# design.net
KiCad netlist of a schematic drawn in Altium Designer
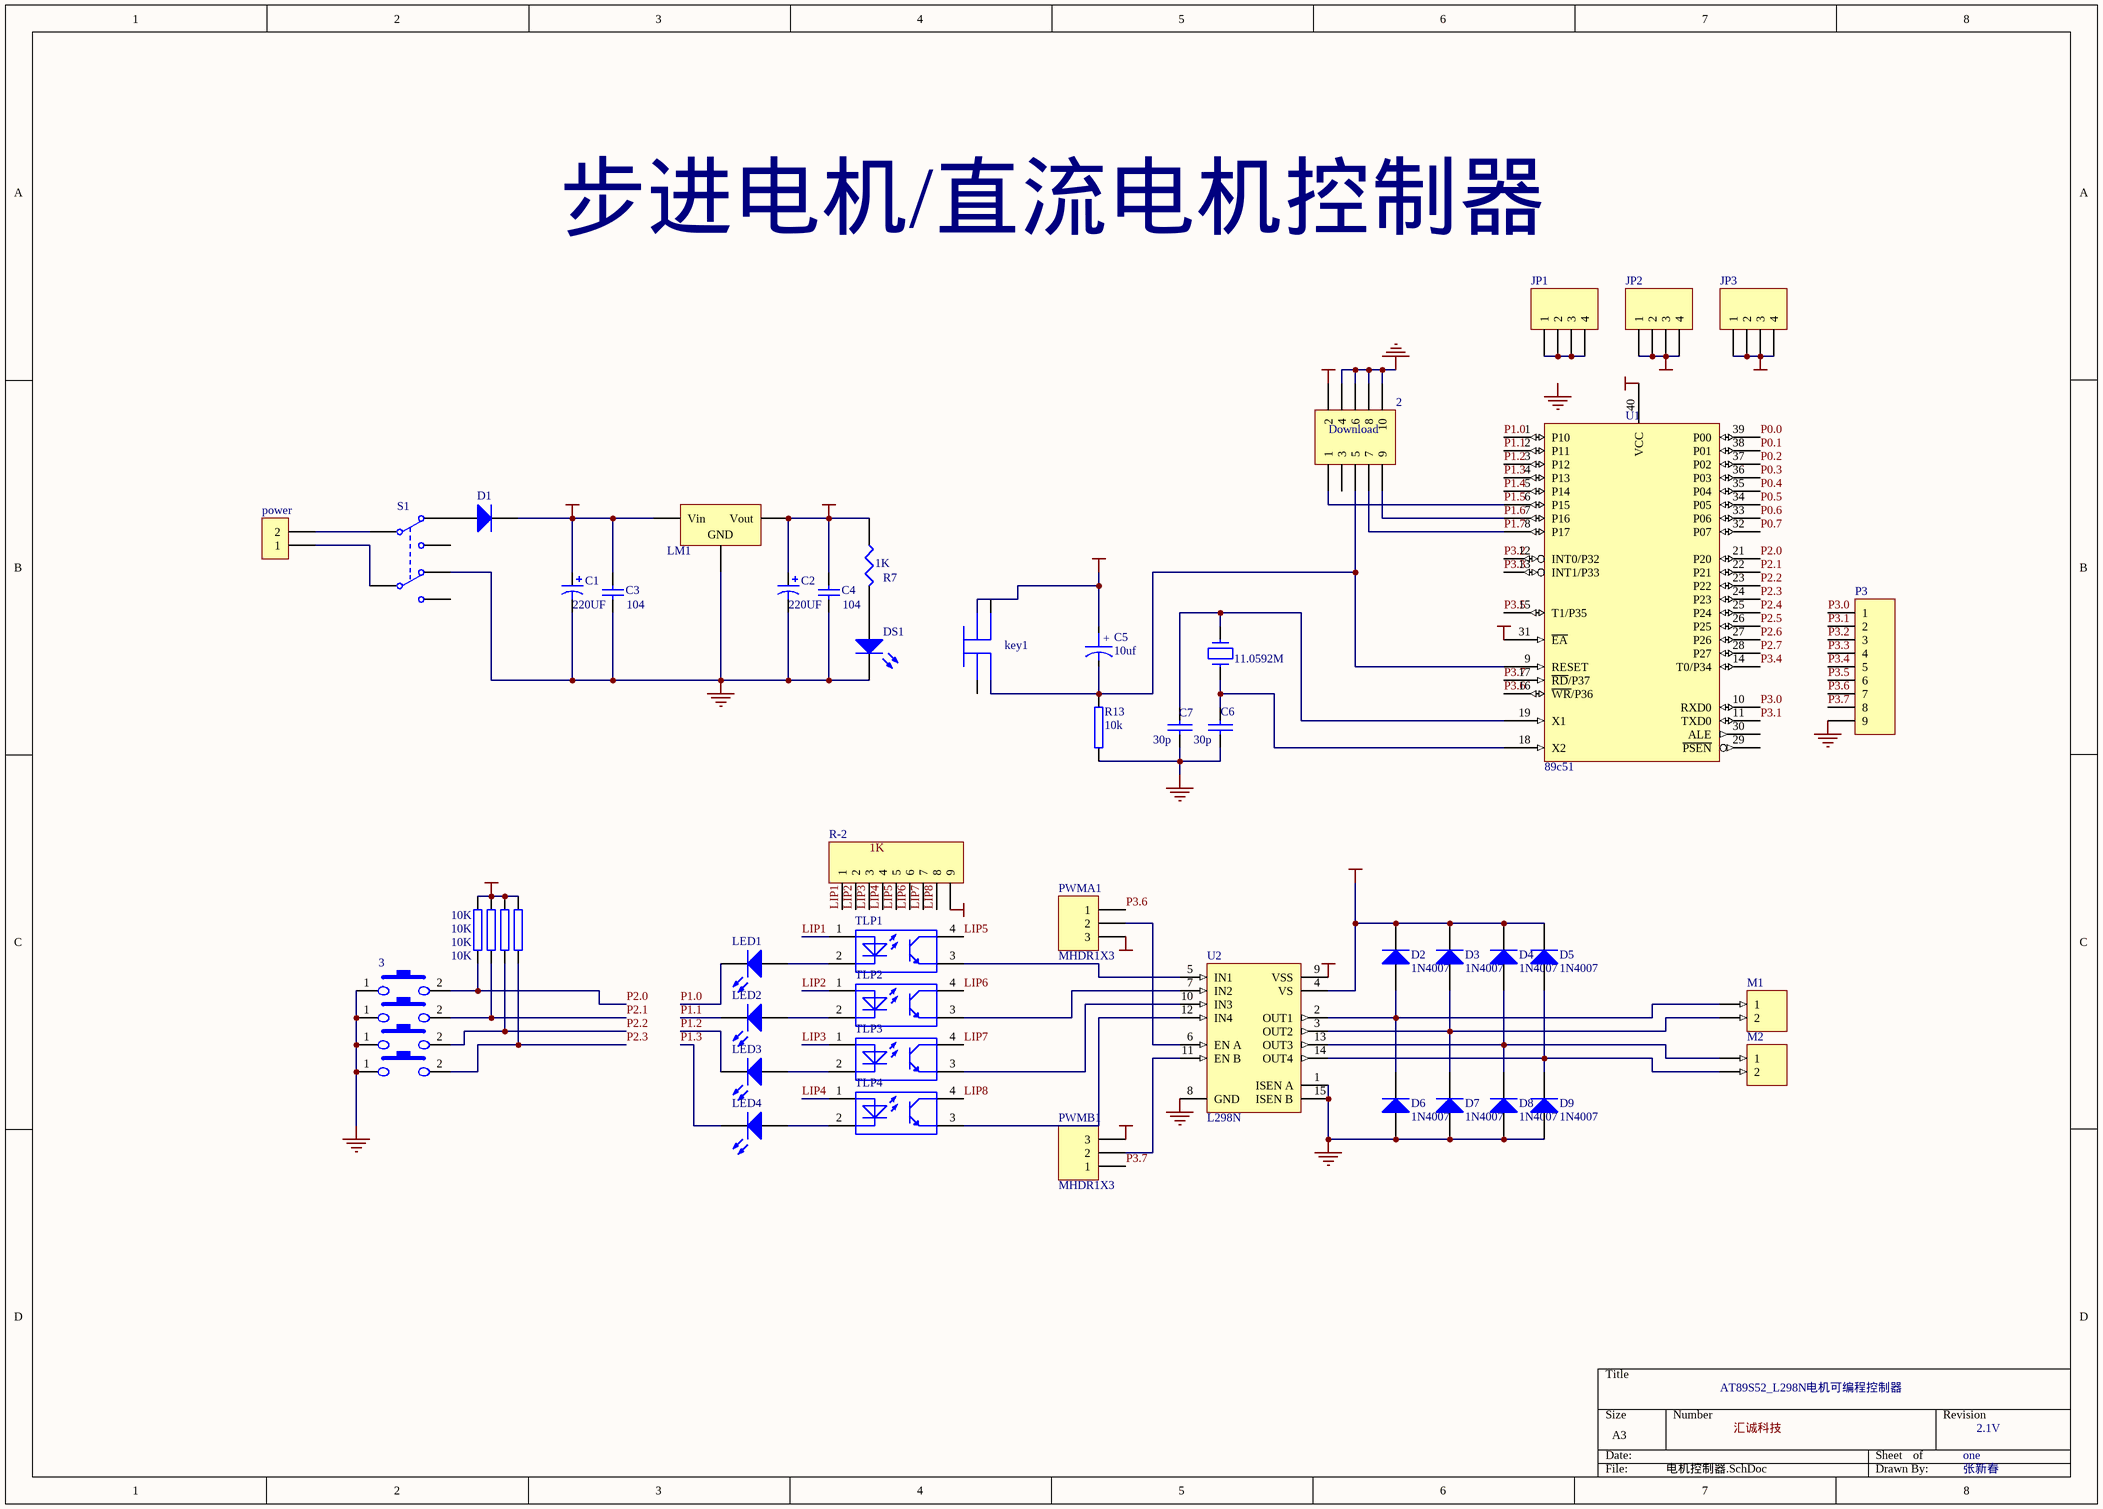
[diagram p0: 电机控制器.SchDoc]

(export (version "E")
  (design (tool "Eeschema 10.0.6"))
  (components
    (comp (ref "1")
      (value "power")
      (footprint "jiechajian:DZ-2")
      (libsource (lib "OldCow1 (1)") (part "power"))
    )
    (comp (ref "2")
      (value "Download")
      (footprint "HDR2X5")
      (description "Header, 5-Pin, Dual row")
      (fields (field (name "PUBLISHER") "Altium Limited"))
      (libsource (lib "Miscellaneous Connectors") (part "Header 5X2"))
    )
    (comp (ref "3") (value "key1") (footprint "AN66") (libsource (lib "OldCow1 (1)") (part "key")))
    (comp (ref "4") (value "key2") (footprint "AN66") (libsource (lib "OldCow1 (1)") (part "key")))
    (comp (ref "5") (value "key3") (footprint "AN66") (libsource (lib "OldCow1 (1)") (part "key")))
    (comp (ref "6") (value "key4") (footprint "AN66") (libsource (lib "OldCow1 (1)") (part "key")))
    (comp (ref "C1")
      (value "220UF")
      (footprint "CD6")
      (description "Polarized Capacitor (Radial)")
      (fields (field (name "PUBLISHER") "Altium Limited"))
      (libsource (lib "Miscellaneous Devices") (part "Cap Pol1"))
    )
    (comp (ref "C2")
      (value "220UF")
      (footprint "CD4")
      (description "Polarized Capacitor (Radial)")
      (fields (field (name "PUBLISHER") "Altium Limited"))
      (libsource (lib "Miscellaneous Devices") (part "Cap Pol1"))
    )
    (comp (ref "C3")
      (value "104")
      (footprint "HDR1X2")
      (description "Capacitor")
      (fields (field (name "PUBLISHER") "Altium Limited"))
      (libsource (lib "Miscellaneous Devices") (part "Cap"))
    )
    (comp (ref "C4")
      (value "104")
      (footprint "HDR1X2")
      (description "Capacitor")
      (fields (field (name "PUBLISHER") "Altium Limited"))
      (libsource (lib "Miscellaneous Devices") (part "Cap"))
    )
    (comp (ref "C5")
      (value "10uf")
      (footprint "CD5")
      (description "Capacitor")
      (libsource (lib "*") (part "CAPACITOR POL"))
    )
    (comp (ref "C6")
      (value "30p")
      (footprint "C1608-0603")
      (description "Capacitor")
      (libsource (lib "*") (part "CAP"))
    )
    (comp (ref "C7")
      (value "30p")
      (footprint "C1608-0603")
      (description "Capacitor")
      (libsource (lib "*") (part "CAP"))
    )
    (comp (ref "D1")
      (value "~")
      (footprint "DIO10.46-5.3x2.8")
      (description "1 Amp General Purpose Rectifier")
      (fields (field (name "PUBLISHER") "Altium Limited"))
      (libsource (lib "Miscellaneous Devices") (part "Diode 1N4007"))
    )
    (comp (ref "D2")
      (value "1N4007")
      (footprint "DIO7.8-4.6x2")
      (description "1 Amp General Purpose Rectifier")
      (fields (field (name "PUBLISHER") "Altium Limited"))
      (libsource (lib "Miscellaneous Devices") (part "Diode 1N4007"))
    )
    (comp (ref "D3")
      (value "1N4007")
      (footprint "DIO7.8-4.6x2")
      (description "1 Amp General Purpose Rectifier")
      (fields (field (name "PUBLISHER") "Altium Limited"))
      (libsource (lib "Miscellaneous Devices") (part "Diode 1N4007"))
    )
    (comp (ref "D4")
      (value "1N4007")
      (footprint "DIO7.8-4.6x2")
      (description "1 Amp General Purpose Rectifier")
      (fields (field (name "PUBLISHER") "Altium Limited"))
      (libsource (lib "Miscellaneous Devices") (part "Diode 1N4007"))
    )
    (comp (ref "D5")
      (value "1N4007")
      (footprint "DIO7.8-4.6x2")
      (description "1 Amp General Purpose Rectifier")
      (fields (field (name "PUBLISHER") "Altium Limited"))
      (libsource (lib "Miscellaneous Devices") (part "Diode 1N4007"))
    )
    (comp (ref "D6")
      (value "1N4007")
      (footprint "DIO7.8-4.6x2")
      (description "1 Amp General Purpose Rectifier")
      (fields (field (name "PUBLISHER") "Altium Limited"))
      (libsource (lib "Miscellaneous Devices") (part "Diode 1N4007"))
    )
    (comp (ref "D7")
      (value "1N4007")
      (footprint "DIO7.8-4.6x2")
      (description "1 Amp General Purpose Rectifier")
      (fields (field (name "PUBLISHER") "Altium Limited"))
      (libsource (lib "Miscellaneous Devices") (part "Diode 1N4007"))
    )
    (comp (ref "D8")
      (value "1N4007")
      (footprint "DIO7.8-4.6x2")
      (description "1 Amp General Purpose Rectifier")
      (fields (field (name "PUBLISHER") "Altium Limited"))
      (libsource (lib "Miscellaneous Devices") (part "Diode 1N4007"))
    )
    (comp (ref "D9")
      (value "1N4007")
      (footprint "DIO7.8-4.6x2")
      (description "1 Amp General Purpose Rectifier")
      (fields (field (name "PUBLISHER") "Altium Limited"))
      (libsource (lib "Miscellaneous Devices") (part "Diode 1N4007"))
    )
    (comp (ref "DS1")
      (value "~")
      (footprint "HDR1X2")
      (description "Typical INFRARED GaAs LED")
      (fields (field (name "PUBLISHER") "Altium Limited"))
      (libsource (lib "Miscellaneous Devices") (part "LED0"))
    )
    (comp (ref "JP1")
      (value "~")
      (footprint "HDR1X4")
      (description "Header, 4-Pin")
      (fields (field (name "PUBLISHER") "Altium Limited"))
      (libsource (lib "Miscellaneous Connectors") (part "Header 4"))
    )
    (comp (ref "JP2")
      (value "~")
      (footprint "HDR1X4")
      (description "Header, 4-Pin")
      (fields (field (name "PUBLISHER") "Altium Limited"))
      (libsource (lib "Miscellaneous Connectors") (part "Header 4"))
    )
    (comp (ref "JP3")
      (value "~")
      (footprint "HDR1X4")
      (description "Header, 4-Pin")
      (fields (field (name "PUBLISHER") "Altium Limited"))
      (libsource (lib "Miscellaneous Connectors") (part "Header 4"))
    )
    (comp (ref "key1") (value "KEY") (footprint "AN66") (libsource (lib "OldCow1 (1)") (part "KEY")))
    (comp (ref "LED1")
      (value "~")
      (footprint "HDR1X2")
      (description "Typical BLUE SiC LED")
      (fields (field (name "PUBLISHER") "Altium Limited"))
      (libsource (lib "Miscellaneous Devices") (part "LED3"))
    )
    (comp (ref "LED2")
      (value "~")
      (footprint "HDR1X2")
      (description "Typical BLUE SiC LED")
      (fields (field (name "PUBLISHER") "Altium Limited"))
      (libsource (lib "Miscellaneous Devices") (part "LED3"))
    )
    (comp (ref "LED3")
      (value "~")
      (footprint "HDR1X2")
      (description "Typical BLUE SiC LED")
      (fields (field (name "PUBLISHER") "Altium Limited"))
      (libsource (lib "Miscellaneous Devices") (part "LED3"))
    )
    (comp (ref "LED4")
      (value "~")
      (footprint "HDR1X2")
      (description "Typical BLUE SiC LED")
      (fields (field (name "PUBLISHER") "Altium Limited"))
      (libsource (lib "Miscellaneous Devices") (part "LED3"))
    )
    (comp (ref "LM1")
      (value "~")
      (footprint "wyk")
      (description "Voltage Regulator")
      (fields (field (name "PUBLISHER") "Altium Limited"))
      (libsource (lib "Miscellaneous Devices") (part "Volt Reg"))
    )
    (comp (ref "M1")
      (value "~")
      (footprint "DZ-2")
      (description "Header, 2-Pin")
      (fields (field (name "PUBLISHER") "Altium Limited"))
      (libsource (lib "Miscellaneous Connectors") (part "MHDR1X2"))
    )
    (comp (ref "M2")
      (value "~")
      (footprint "jiechajian:DZ-2")
      (description "Header, 2-Pin")
      (fields (field (name "PUBLISHER") "Altium Limited"))
      (libsource (lib "Miscellaneous Connectors") (part "MHDR1X2"))
    )
    (comp (ref "P3")
      (value "~")
      (footprint "HDR1X9")
      (description "Header, 9-Pin")
      (fields (field (name "PUBLISHER") "Altium Limited"))
      (libsource (lib "Miscellaneous Connectors") (part "Header 9"))
    )
    (comp (ref "PWMA1")
      (value "MHDR1X3")
      (footprint "MHDR1X3")
      (description "Header, 3-Pin")
      (fields (field (name "PUBLISHER") "Altium Limited"))
      (libsource (lib "Miscellaneous Connectors") (part "MHDR1X3"))
    )
    (comp (ref "PWMB1")
      (value "MHDR1X3")
      (footprint "MHDR1X3")
      (description "Header, 3-Pin")
      (fields (field (name "PUBLISHER") "Altium Limited"))
      (libsource (lib "") (part "MHDR1X3_1"))
    )
    (comp (ref "R-2")
      (value "~")
      (footprint "HDR1X9")
      (description "Header, 9-Pin")
      (fields (field (name "PUBLISHER") "Altium Limited"))
      (libsource (lib "") (part "Header 9_1"))
    )
    (comp (ref "R7") (value "1K") (footprint "HDR1X2") (libsource (lib "*") (part "RES1")))
    (comp (ref "R13") (value "10k") (footprint "INDC2012-0805") (libsource (lib "*") (part "RES2")))
    (comp (ref "R15") (value "10K") (footprint "INDC2012-0805") (libsource (lib "*") (part "RES2")))
    (comp (ref "R16") (value "10K") (footprint "INDC2012-0805") (libsource (lib "*") (part "RES2")))
    (comp (ref "R17") (value "10K") (footprint "INDC2012-0805") (libsource (lib "*") (part "RES2")))
    (comp (ref "R18") (value "10K") (footprint "INDC2012-0805") (libsource (lib "*") (part "RES2")))
    (comp (ref "S1")
      (value "~")
      (footprint "DPDT-6")
      (description "Switch")
      (fields (field (name "PUBLISHER") "Altium Limited"))
      (libsource (lib "Miscellaneous Devices") (part "SW DPDT"))
    )
    (comp (ref "TLP1") (value "~") (footprint "DIP4") (libsource (lib "MyInt_Lib") (part "TLP521-1")))
    (comp (ref "TLP2") (value "~") (footprint "DIP4") (libsource (lib "MyInt_Lib") (part "TLP521-1")))
    (comp (ref "TLP3") (value "~") (footprint "DIP4") (libsource (lib "MyInt_Lib") (part "TLP521-1")))
    (comp (ref "TLP4") (value "~") (footprint "DIP4") (libsource (lib "MyInt_Lib") (part "TLP521-1")))
    (comp (ref "U1") (value "89c51") (footprint "DIP40") (libsource (lib "OldCow1 (2)") (part "8051")))
    (comp (ref "U2")
      (value "L298N")
      (footprint "DFM-T15/X1.6V")
      (description "Dual Full Bridge Driver")
      (fields (field (name "PUBLISHER") "Altium Limited"))
      (libsource (lib "ST Interface DC Motor Controller") (part "L298N"))
    )
    (comp (ref "Y1")
      (value "11.0592M")
      (footprint "SPST-2")
      (description "Crystal")
      (libsource (lib "*") (part "CRYSTAL"))
    )
  )
  (nets
    (net (code "1") (name "+5V") (class "Default")
      (node (ref "2") (pin "2") (pinfunction "2_2") (pintype "passive"))
      (node (ref "C2") (pin "1") (pinfunction "1_1") (pintype "passive"))
      (node (ref "C4") (pin "2") (pinfunction "2_2") (pintype "passive"))
      (node (ref "C5") (pin "1") (pinfunction "1_1") (pintype "passive"))
      (node (ref "JP2") (pin "1") (pinfunction "1_1") (pintype "passive"))
      (node (ref "JP2") (pin "2") (pinfunction "2_2") (pintype "passive"))
      (node (ref "JP2") (pin "3") (pinfunction "3_3") (pintype "passive"))
      (node (ref "JP2") (pin "4") (pinfunction "4_4") (pintype "passive"))
      (node (ref "LM1") (pin "3") (pinfunction "Vout_3") (pintype "passive"))
      (node (ref "PWMA1") (pin "3") (pinfunction "3_3") (pintype "passive"))
      (node (ref "PWMB1") (pin "3") (pinfunction "3_3") (pintype "passive"))
      (node (ref "R-2") (pin "9") (pinfunction "9_9") (pintype "passive"))
      (node (ref "R15") (pin "2") (pinfunction "2_2") (pintype "passive"))
      (node (ref "R16") (pin "2") (pinfunction "2_2") (pintype "passive"))
      (node (ref "R17") (pin "2") (pinfunction "2_2") (pintype "passive"))
      (node (ref "R18") (pin "2") (pinfunction "2_2") (pintype "passive"))
      (node (ref "R7") (pin "1") (pinfunction "1_1") (pintype "passive"))
      (node (ref "U1") (pin "31") (pinfunction "~{EA}_31") (pintype "input"))
      (node (ref "U1") (pin "40") (pinfunction "VCC_40") (pintype "power_in"))
      (node (ref "U2") (pin "9") (pinfunction "VSS_9") (pintype "power_in"))
      (node (ref "key1") (pin "1") (pinfunction "1_1") (pintype "passive"))
    )
    (net (code "2") (name "+12V") (class "Default")
      (node (ref "C1") (pin "1") (pinfunction "1_1") (pintype "passive"))
      (node (ref "C3") (pin "2") (pinfunction "2_2") (pintype "passive"))
      (node (ref "D1") (pin "2") (pinfunction "K_2") (pintype "passive"))
      (node (ref "D2") (pin "2") (pinfunction "K_2") (pintype "passive"))
      (node (ref "D3") (pin "2") (pinfunction "K_2") (pintype "passive"))
      (node (ref "D4") (pin "2") (pinfunction "K_2") (pintype "passive"))
      (node (ref "D5") (pin "2") (pinfunction "K_2") (pintype "passive"))
      (node (ref "JP3") (pin "1") (pinfunction "1_1") (pintype "passive"))
      (node (ref "JP3") (pin "2") (pinfunction "2_2") (pintype "passive"))
      (node (ref "JP3") (pin "3") (pinfunction "3_3") (pintype "passive"))
      (node (ref "JP3") (pin "4") (pinfunction "4_4") (pintype "passive"))
      (node (ref "LM1") (pin "1") (pinfunction "Vin_1") (pintype "passive"))
      (node (ref "U2") (pin "4") (pinfunction "VS_4") (pintype "power_in"))
    )
    (net (code "5") (name "/LIP1") (class "Default")
      (node (ref "R-2") (pin "1") (pinfunction "1_1") (pintype "passive"))
      (node (ref "TLP1") (pin "1") (pinfunction "1_1") (pintype "passive"))
    )
    (net (code "6") (name "/LIP2") (class "Default")
      (node (ref "R-2") (pin "2") (pinfunction "2_2") (pintype "passive"))
      (node (ref "TLP2") (pin "1") (pinfunction "1_1") (pintype "passive"))
    )
    (net (code "7") (name "/LIP3") (class "Default")
      (node (ref "R-2") (pin "3") (pinfunction "3_3") (pintype "passive"))
      (node (ref "TLP3") (pin "1") (pinfunction "1_1") (pintype "passive"))
    )
    (net (code "8") (name "/LIP4") (class "Default")
      (node (ref "R-2") (pin "4") (pinfunction "4_4") (pintype "passive"))
      (node (ref "TLP4") (pin "1") (pinfunction "1_1") (pintype "passive"))
    )
    (net (code "9") (name "/LIP5") (class "Default")
      (node (ref "R-2") (pin "5") (pinfunction "5_5") (pintype "passive"))
      (node (ref "TLP1") (pin "4") (pinfunction "4_4") (pintype "passive"))
    )
    (net (code "10") (name "/LIP6") (class "Default")
      (node (ref "R-2") (pin "6") (pinfunction "6_6") (pintype "passive"))
      (node (ref "TLP2") (pin "4") (pinfunction "4_4") (pintype "passive"))
    )
    (net (code "11") (name "/LIP7") (class "Default")
      (node (ref "R-2") (pin "7") (pinfunction "7_7") (pintype "passive"))
      (node (ref "TLP3") (pin "4") (pinfunction "4_4") (pintype "passive"))
    )
    (net (code "12") (name "/LIP8") (class "Default")
      (node (ref "R-2") (pin "8") (pinfunction "8_8") (pintype "passive"))
      (node (ref "TLP4") (pin "4") (pinfunction "4_4") (pintype "passive"))
    )
    (net (code "13") (name "/P0.0") (class "Default")
      (node (ref "U1") (pin "39") (pinfunction "P00_39") (pintype "bidirectional"))
    )
    (net (code "14") (name "/P0.1") (class "Default")
      (node (ref "U1") (pin "38") (pinfunction "P01_38") (pintype "bidirectional"))
    )
    (net (code "15") (name "/P0.2") (class "Default")
      (node (ref "U1") (pin "37") (pinfunction "P02_37") (pintype "bidirectional"))
    )
    (net (code "16") (name "/P0.3") (class "Default")
      (node (ref "U1") (pin "36") (pinfunction "P03_36") (pintype "bidirectional"))
    )
    (net (code "17") (name "/P0.4") (class "Default")
      (node (ref "U1") (pin "35") (pinfunction "P04_35") (pintype "bidirectional"))
    )
    (net (code "18") (name "/P0.5") (class "Default")
      (node (ref "U1") (pin "34") (pinfunction "P05_34") (pintype "bidirectional"))
    )
    (net (code "19") (name "/P0.6") (class "Default")
      (node (ref "U1") (pin "33") (pinfunction "P06_33") (pintype "bidirectional"))
    )
    (net (code "20") (name "/P0.7") (class "Default")
      (node (ref "U1") (pin "32") (pinfunction "P07_32") (pintype "bidirectional"))
    )
    (net (code "21") (name "/P1.0") (class "Default")
      (node (ref "LED1") (pin "2") (pinfunction "K_2") (pintype "passive"))
      (node (ref "U1") (pin "1") (pinfunction "P10_1") (pintype "bidirectional"))
    )
    (net (code "22") (name "/P1.1") (class "Default")
      (node (ref "LED2") (pin "2") (pinfunction "K_2") (pintype "passive"))
      (node (ref "U1") (pin "2") (pinfunction "P11_2") (pintype "bidirectional"))
    )
    (net (code "23") (name "/P1.2") (class "Default")
      (node (ref "LED3") (pin "2") (pinfunction "K_2") (pintype "passive"))
      (node (ref "U1") (pin "3") (pinfunction "P12_3") (pintype "bidirectional"))
    )
    (net (code "24") (name "/P1.3") (class "Default")
      (node (ref "LED4") (pin "2") (pinfunction "K_2") (pintype "passive"))
      (node (ref "U1") (pin "4") (pinfunction "P13_4") (pintype "bidirectional"))
    )
    (net (code "25") (name "/P1.4") (class "Default")
      (node (ref "U1") (pin "5") (pinfunction "P14_5") (pintype "bidirectional"))
    )
    (net (code "26") (name "/P1.5") (class "Default")
      (node (ref "2") (pin "1") (pinfunction "1_1") (pintype "passive"))
      (node (ref "U1") (pin "6") (pinfunction "P15_6") (pintype "bidirectional"))
    )
    (net (code "27") (name "/P1.6") (class "Default")
      (node (ref "2") (pin "9") (pinfunction "9_9") (pintype "passive"))
      (node (ref "U1") (pin "7") (pinfunction "P16_7") (pintype "bidirectional"))
    )
    (net (code "28") (name "/P1.7") (class "Default")
      (node (ref "2") (pin "7") (pinfunction "7_7") (pintype "passive"))
      (node (ref "U1") (pin "8") (pinfunction "P17_8") (pintype "bidirectional"))
    )
    (net (code "29") (name "/P2.0") (class "Default")
      (node (ref "3") (pin "2") (pinfunction "2_2") (pintype "passive"))
      (node (ref "R17") (pin "1") (pinfunction "1_1") (pintype "passive"))
      (node (ref "U1") (pin "21") (pinfunction "P20_21") (pintype "bidirectional"))
    )
    (net (code "30") (name "/P2.1") (class "Default")
      (node (ref "4") (pin "2") (pinfunction "2_2") (pintype "passive"))
      (node (ref "R18") (pin "1") (pinfunction "1_1") (pintype "passive"))
      (node (ref "U1") (pin "22") (pinfunction "P21_22") (pintype "bidirectional"))
    )
    (net (code "31") (name "/P2.2") (class "Default")
      (node (ref "5") (pin "2") (pinfunction "2_2") (pintype "passive"))
      (node (ref "R15") (pin "1") (pinfunction "1_1") (pintype "passive"))
      (node (ref "U1") (pin "23") (pinfunction "P22_23") (pintype "bidirectional"))
    )
    (net (code "32") (name "/P2.3") (class "Default")
      (node (ref "6") (pin "2") (pinfunction "2_2") (pintype "passive"))
      (node (ref "R16") (pin "1") (pinfunction "1_1") (pintype "passive"))
      (node (ref "U1") (pin "24") (pinfunction "P23_24") (pintype "bidirectional"))
    )
    (net (code "33") (name "/P2.4") (class "Default")
      (node (ref "U1") (pin "25") (pinfunction "P24_25") (pintype "bidirectional"))
    )
    (net (code "34") (name "/P2.5") (class "Default")
      (node (ref "U1") (pin "26") (pinfunction "P25_26") (pintype "bidirectional"))
    )
    (net (code "35") (name "/P2.6") (class "Default")
      (node (ref "U1") (pin "27") (pinfunction "P26_27") (pintype "bidirectional"))
    )
    (net (code "36") (name "/P2.7") (class "Default")
      (node (ref "U1") (pin "28") (pinfunction "P27_28") (pintype "bidirectional"))
    )
    (net (code "37") (name "/P3.0") (class "Default")
      (node (ref "P3") (pin "1") (pinfunction "1_1") (pintype "passive"))
      (node (ref "U1") (pin "10") (pinfunction "RXD0_10") (pintype "bidirectional"))
    )
    (net (code "38") (name "/P3.1") (class "Default")
      (node (ref "P3") (pin "2") (pinfunction "2_2") (pintype "passive"))
      (node (ref "U1") (pin "11") (pinfunction "TXD0_11") (pintype "bidirectional"))
    )
    (net (code "39") (name "/P3.2") (class "Default")
      (node (ref "P3") (pin "3") (pinfunction "3_3") (pintype "passive"))
      (node (ref "U1") (pin "12") (pinfunction "INT0/P32_12") (pintype "bidirectional"))
    )
    (net (code "40") (name "/P3.3") (class "Default")
      (node (ref "P3") (pin "4") (pinfunction "4_4") (pintype "passive"))
      (node (ref "U1") (pin "13") (pinfunction "INT1/P33_13") (pintype "bidirectional"))
    )
    (net (code "41") (name "/P3.4") (class "Default")
      (node (ref "P3") (pin "5") (pinfunction "5_5") (pintype "passive"))
      (node (ref "U1") (pin "14") (pinfunction "T0/P34_14") (pintype "bidirectional"))
    )
    (net (code "42") (name "/P3.5") (class "Default")
      (node (ref "P3") (pin "6") (pinfunction "6_6") (pintype "passive"))
      (node (ref "U1") (pin "15") (pinfunction "T1/P35_15") (pintype "bidirectional"))
    )
    (net (code "43") (name "/P3.6") (class "Default")
      (node (ref "P3") (pin "7") (pinfunction "7_7") (pintype "passive"))
      (node (ref "PWMA1") (pin "1") (pinfunction "1_1") (pintype "passive"))
      (node (ref "U1") (pin "16") (pinfunction "~{WR}/P36_16") (pintype "bidirectional"))
    )
    (net (code "44") (name "/P3.7") (class "Default")
      (node (ref "P3") (pin "8") (pinfunction "8_8") (pintype "passive"))
      (node (ref "PWMB1") (pin "1") (pinfunction "1_1") (pintype "passive"))
      (node (ref "U1") (pin "17") (pinfunction "~{RD}/P37_17") (pintype "input"))
    )
    (net (code "46") (name "GND") (class "Default")
      (node (ref "2") (pin "10") (pinfunction "10_10") (pintype "passive"))
      (node (ref "2") (pin "4") (pinfunction "4_4") (pintype "passive"))
      (node (ref "2") (pin "6") (pinfunction "6_6") (pintype "passive"))
      (node (ref "2") (pin "8") (pinfunction "8_8") (pintype "passive"))
      (node (ref "3") (pin "1") (pinfunction "1_1") (pintype "passive"))
      (node (ref "4") (pin "1") (pinfunction "1_1") (pintype "passive"))
      (node (ref "5") (pin "1") (pinfunction "1_1") (pintype "passive"))
      (node (ref "6") (pin "1") (pinfunction "1_1") (pintype "passive"))
      (node (ref "C1") (pin "2") (pinfunction "2_2") (pintype "passive"))
      (node (ref "C2") (pin "2") (pinfunction "2_2") (pintype "passive"))
      (node (ref "C3") (pin "1") (pinfunction "1_1") (pintype "passive"))
      (node (ref "C4") (pin "1") (pinfunction "1_1") (pintype "passive"))
      (node (ref "C6") (pin "2") (pinfunction "2_2") (pintype "passive"))
      (node (ref "C7") (pin "2") (pinfunction "2_2") (pintype "passive"))
      (node (ref "D6") (pin "1") (pinfunction "A_1") (pintype "passive"))
      (node (ref "D7") (pin "1") (pinfunction "A_1") (pintype "passive"))
      (node (ref "D8") (pin "1") (pinfunction "A_1") (pintype "passive"))
      (node (ref "D9") (pin "1") (pinfunction "A_1") (pintype "passive"))
      (node (ref "DS1") (pin "2") (pinfunction "K_2") (pintype "passive"))
      (node (ref "LM1") (pin "2") (pinfunction "GND_2") (pintype "passive"))
      (node (ref "P3") (pin "9") (pinfunction "9_9") (pintype "passive"))
      (node (ref "R13") (pin "2") (pinfunction "2_2") (pintype "passive"))
      (node (ref "S1") (pin "4") (pinfunction "NC2_4") (pintype "passive"))
      (node (ref "U1") (pin "20") (pinfunction "GND_20") (pintype "power_in"))
      (node (ref "U2") (pin "1") (pinfunction "ISEN_A_1") (pintype "passive"))
      (node (ref "U2") (pin "15") (pinfunction "ISEN_B_15") (pintype "passive"))
      (node (ref "U2") (pin "8") (pinfunction "GND_8") (pintype "power_in"))
    )
    (net (code "47") (name "Net-(D1-A)") (class "Default")
      (node (ref "D1") (pin "1") (pinfunction "A_1") (pintype "passive"))
      (node (ref "S1") (pin "2") (pinfunction "NC1_2") (pintype "passive"))
    )
    (net (code "48") (name "Net-(D2-A)") (class "Default")
      (node (ref "D2") (pin "1") (pinfunction "A_1") (pintype "passive"))
      (node (ref "D6") (pin "2") (pinfunction "K_2") (pintype "passive"))
      (node (ref "M1") (pin "1") (pinfunction "1_1") (pintype "input"))
      (node (ref "U2") (pin "2") (pinfunction "OUT1_2") (pintype "output"))
    )
    (net (code "49") (name "Net-(D3-A)") (class "Default")
      (node (ref "D3") (pin "1") (pinfunction "A_1") (pintype "passive"))
      (node (ref "D7") (pin "2") (pinfunction "K_2") (pintype "passive"))
      (node (ref "M1") (pin "2") (pinfunction "2_2") (pintype "input"))
      (node (ref "U2") (pin "3") (pinfunction "OUT2_3") (pintype "output"))
    )
    (net (code "50") (name "Net-(D4-A)") (class "Default")
      (node (ref "D4") (pin "1") (pinfunction "A_1") (pintype "passive"))
      (node (ref "D8") (pin "2") (pinfunction "K_2") (pintype "passive"))
      (node (ref "M2") (pin "1") (pinfunction "1_1") (pintype "input"))
      (node (ref "U2") (pin "13") (pinfunction "OUT3_13") (pintype "output"))
    )
    (net (code "51") (name "Net-(D5-A)") (class "Default")
      (node (ref "D5") (pin "1") (pinfunction "A_1") (pintype "passive"))
      (node (ref "D9") (pin "2") (pinfunction "K_2") (pintype "passive"))
      (node (ref "M2") (pin "2") (pinfunction "2_2") (pintype "input"))
      (node (ref "U2") (pin "14") (pinfunction "OUT4_14") (pintype "output"))
    )
    (net (code "52") (name "Net-(DS1-A)") (class "Default")
      (node (ref "DS1") (pin "1") (pinfunction "A_1") (pintype "passive"))
      (node (ref "R7") (pin "2") (pinfunction "2_2") (pintype "passive"))
    )
    (net (code "53") (name "Net-(JP1-Pad1)") (class "Default")
      (node (ref "JP1") (pin "1") (pinfunction "1_1") (pintype "passive"))
      (node (ref "JP1") (pin "2") (pinfunction "2_2") (pintype "passive"))
      (node (ref "JP1") (pin "3") (pinfunction "3_3") (pintype "passive"))
      (node (ref "JP1") (pin "4") (pinfunction "4_4") (pintype "passive"))
    )
    (net (code "54") (name "Net-(LED1-A)") (class "Default")
      (node (ref "LED1") (pin "1") (pinfunction "A_1") (pintype "passive"))
      (node (ref "TLP1") (pin "2") (pinfunction "2_2") (pintype "passive"))
    )
    (net (code "55") (name "Net-(LED2-A)") (class "Default")
      (node (ref "LED2") (pin "1") (pinfunction "A_1") (pintype "passive"))
      (node (ref "TLP2") (pin "2") (pinfunction "2_2") (pintype "passive"))
    )
    (net (code "56") (name "Net-(LED3-A)") (class "Default")
      (node (ref "LED3") (pin "1") (pinfunction "A_1") (pintype "passive"))
      (node (ref "TLP3") (pin "2") (pinfunction "2_2") (pintype "passive"))
    )
    (net (code "57") (name "Net-(LED4-A)") (class "Default")
      (node (ref "LED4") (pin "1") (pinfunction "A_1") (pintype "passive"))
      (node (ref "TLP4") (pin "2") (pinfunction "2_2") (pintype "passive"))
    )
    (net (code "58") (name "Net-(S1-COMMON1)") (class "Default")
      (node (ref "1") (pin "2") (pinfunction "2_2") (pintype "passive"))
      (node (ref "S1") (pin "1") (pinfunction "COMMON1_1") (pintype "passive"))
    )
    (net (code "59") (name "Net-(S1-COMMON2)") (class "Default")
      (node (ref "1") (pin "1") (pinfunction "1_1") (pintype "passive"))
      (node (ref "S1") (pin "5") (pinfunction "COMMON2_5") (pintype "passive"))
    )
    (net (code "60") (name "Net-(U1-RESET)") (class "Default")
      (node (ref "2") (pin "5") (pinfunction "5_5") (pintype "passive"))
      (node (ref "C5") (pin "2") (pinfunction "2_2") (pintype "passive"))
      (node (ref "R13") (pin "1") (pinfunction "1_1") (pintype "passive"))
      (node (ref "U1") (pin "9") (pinfunction "RESET_9") (pintype "input"))
      (node (ref "key1") (pin "2") (pinfunction "2_2") (pintype "passive"))
    )
    (net (code "61") (name "Net-(U1-X1)") (class "Default")
      (node (ref "C7") (pin "1") (pinfunction "1_1") (pintype "passive"))
      (node (ref "U1") (pin "19") (pinfunction "X1_19") (pintype "input"))
      (node (ref "Y1") (pin "1") (pinfunction "1_1") (pintype "passive"))
    )
    (net (code "62") (name "Net-(U1-X2)") (class "Default")
      (node (ref "C6") (pin "1") (pinfunction "1_1") (pintype "passive"))
      (node (ref "U1") (pin "18") (pinfunction "X2_18") (pintype "input"))
      (node (ref "Y1") (pin "2") (pinfunction "2_2") (pintype "passive"))
    )
    (net (code "63") (name "Net-(U2-EN_A)") (class "Default")
      (node (ref "PWMA1") (pin "2") (pinfunction "2_2") (pintype "passive"))
      (node (ref "U2") (pin "6") (pinfunction "EN_A_6") (pintype "input"))
    )
    (net (code "64") (name "Net-(U2-EN_B)") (class "Default")
      (node (ref "PWMB1") (pin "2") (pinfunction "2_2") (pintype "passive"))
      (node (ref "U2") (pin "11") (pinfunction "EN_B_11") (pintype "input"))
    )
    (net (code "65") (name "Net-(U2-IN1)") (class "Default")
      (node (ref "TLP1") (pin "3") (pinfunction "3_3") (pintype "passive"))
      (node (ref "U2") (pin "5") (pinfunction "IN1_5") (pintype "input"))
    )
    (net (code "66") (name "Net-(U2-IN2)") (class "Default")
      (node (ref "TLP2") (pin "3") (pinfunction "3_3") (pintype "passive"))
      (node (ref "U2") (pin "7") (pinfunction "IN2_7") (pintype "input"))
    )
    (net (code "67") (name "Net-(U2-IN3)") (class "Default")
      (node (ref "TLP3") (pin "3") (pinfunction "3_3") (pintype "passive"))
      (node (ref "U2") (pin "10") (pinfunction "IN3_10") (pintype "input"))
    )
    (net (code "68") (name "Net-(U2-IN4)") (class "Default")
      (node (ref "TLP4") (pin "3") (pinfunction "3_3") (pintype "passive"))
      (node (ref "U2") (pin "12") (pinfunction "IN4_12") (pintype "input"))
    )
    (net (code "69") (name "unconnected-(2-Pad3)") (class "Default")
      (node (ref "2") (pin "3") (pinfunction "3_3") (pintype "passive"))
    )
    (net (code "70") (name "unconnected-(S1-NO1-Pad3)") (class "Default")
      (node (ref "S1") (pin "3") (pinfunction "NO1_3") (pintype "passive"))
    )
    (net (code "71") (name "unconnected-(S1-NO2-Pad6)") (class "Default")
      (node (ref "S1") (pin "6") (pinfunction "NO2_6") (pintype "passive"))
    )
    (net (code "72") (name "unconnected-(U1-ALE-Pad30)") (class "Default")
      (node (ref "U1") (pin "30") (pinfunction "ALE_30") (pintype "output"))
    )
    (net (code "73") (name "unconnected-(U1-~{PSEN}-Pad29)") (class "Default")
      (node (ref "U1") (pin "29") (pinfunction "~{PSEN}_29") (pintype "output"))
    )
    (net (code "74") (name "unconnected-(key1-Pad0)") (class "Default")
      (node (ref "key1") (pin "0") (pinfunction "0_0") (pintype "passive"))
    )
    (net (code "75") (name "unconnected-(key1-Pad3)") (class "Default")
      (node (ref "key1") (pin "3") (pinfunction "3_3") (pintype "passive"))
    )
  )
)
